# schmatic.net
KiCad netlist of a schematic drawn in EasyEDA Pro
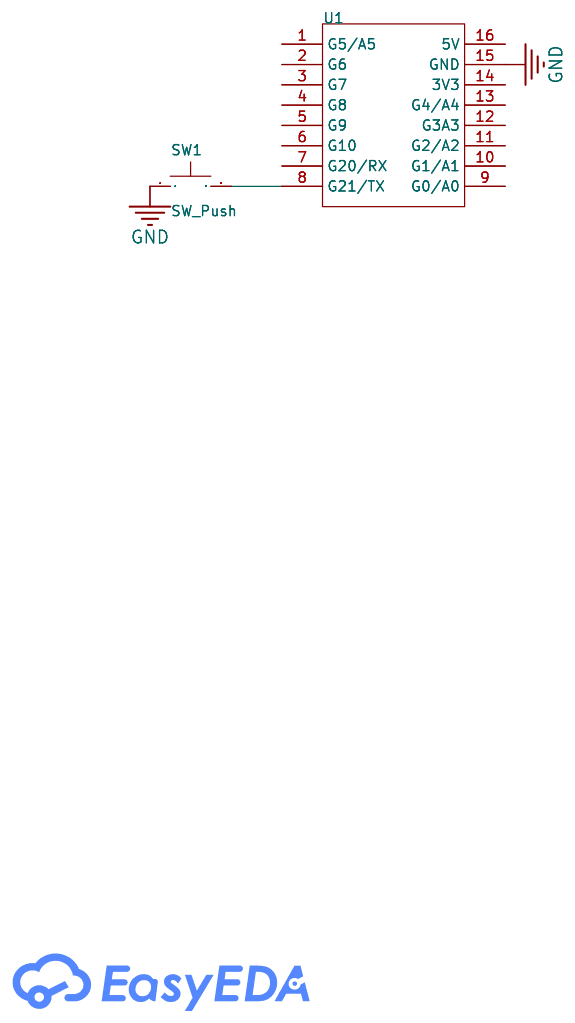
[diagram p0: schematic sheet]

(export (version "E")
  (design (tool "Eeschema 10.0.6"))
  (components
    (comp (ref "SW1")
      (value "SW_Push")
      (footprint "easyedapro:0805")
      (libsource (lib "easyedapro") (part "SW_Push"))
    )
    (comp (ref "U1")
      (value "~")
      (footprint "easyedapro:ESP32 C3 SUPER MINI")
      (libsource (lib "easyedapro") (part "ESP32 C3 SUPER MINI"))
    )
  )
  (nets
    (net (code "1") (name "GND") (class "Default")
      (node (ref "SW1") (pin "1") (pinfunction "1_1") (pintype "input"))
      (node (ref "U1") (pin "15") (pinfunction "GND_15") (pintype "input"))
    )
    (net (code "2") (name "Net-(U1-G21{slash}TX)") (class "Default")
      (node (ref "SW1") (pin "2") (pinfunction "2_2") (pintype "input"))
      (node (ref "U1") (pin "8") (pinfunction "G21/TX_8") (pintype "input"))
    )
    (net (code "3") (name "unconnected-(U1-3V3-Pad14)") (class "Default")
      (node (ref "U1") (pin "14") (pinfunction "3V3_14") (pintype "input"))
    )
    (net (code "4") (name "unconnected-(U1-5V-Pad16)") (class "Default")
      (node (ref "U1") (pin "16") (pinfunction "5V_16") (pintype "input"))
    )
    (net (code "5") (name "unconnected-(U1-G0{slash}A0-Pad9)") (class "Default")
      (node (ref "U1") (pin "9") (pinfunction "G0/A0_9") (pintype "input"))
    )
    (net (code "6") (name "unconnected-(U1-G1{slash}A1-Pad10)") (class "Default")
      (node (ref "U1") (pin "10") (pinfunction "G1/A1_10") (pintype "input"))
    )
    (net (code "7") (name "unconnected-(U1-G2{slash}A2-Pad11)") (class "Default")
      (node (ref "U1") (pin "11") (pinfunction "G2/A2_11") (pintype "input"))
    )
    (net (code "8") (name "unconnected-(U1-G3A3-Pad12)") (class "Default")
      (node (ref "U1") (pin "12") (pinfunction "G3A3_12") (pintype "input"))
    )
    (net (code "9") (name "unconnected-(U1-G4{slash}A4-Pad13)") (class "Default")
      (node (ref "U1") (pin "13") (pinfunction "G4/A4_13") (pintype "input"))
    )
    (net (code "10") (name "unconnected-(U1-G5{slash}A5-Pad1)") (class "Default")
      (node (ref "U1") (pin "1") (pinfunction "G5/A5_1") (pintype "input"))
    )
    (net (code "11") (name "unconnected-(U1-G6-Pad2)") (class "Default")
      (node (ref "U1") (pin "2") (pinfunction "G6_2") (pintype "input"))
    )
    (net (code "12") (name "unconnected-(U1-G7-Pad3)") (class "Default")
      (node (ref "U1") (pin "3") (pinfunction "G7_3") (pintype "input"))
    )
    (net (code "13") (name "unconnected-(U1-G8-Pad4)") (class "Default")
      (node (ref "U1") (pin "4") (pinfunction "G8_4") (pintype "input"))
    )
    (net (code "14") (name "unconnected-(U1-G9-Pad5)") (class "Default")
      (node (ref "U1") (pin "5") (pinfunction "G9_5") (pintype "input"))
    )
    (net (code "15") (name "unconnected-(U1-G10-Pad6)") (class "Default")
      (node (ref "U1") (pin "6") (pinfunction "G10_6") (pintype "input"))
    )
    (net (code "16") (name "unconnected-(U1-G20{slash}RX-Pad7)") (class "Default")
      (node (ref "U1") (pin "7") (pinfunction "G20/RX_7") (pintype "input"))
    )
  )
)
